# saturation_main.net
KiCad netlist of a schematic drawn in EAGLE
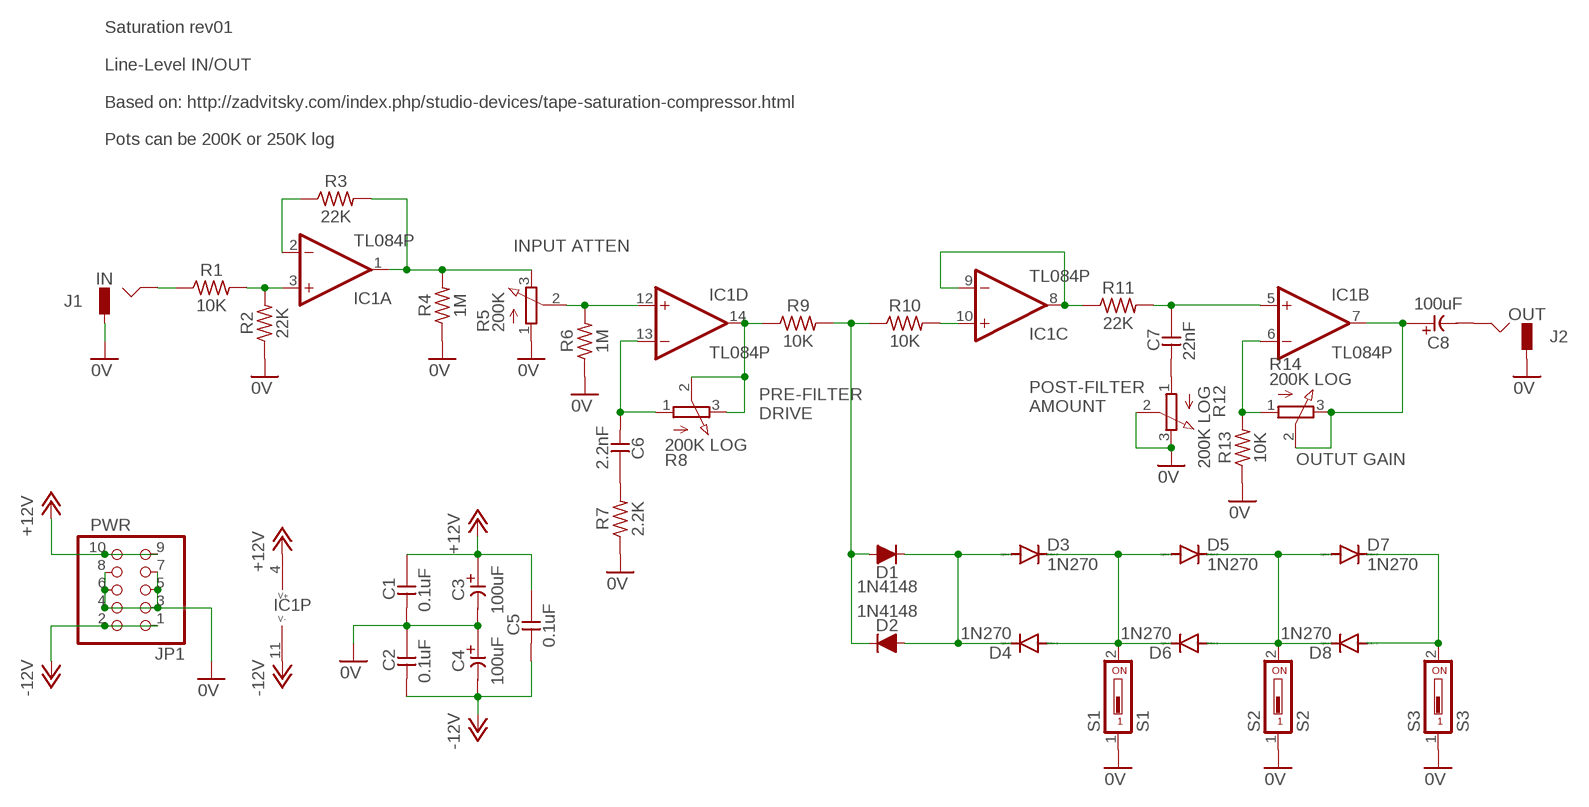
[diagram p0: schematic, sheet 1]

(export (version "E")
  (design (tool "Eeschema 10.0.6"))
  (components
    (comp (ref "C1")
      (value "0.1uF")
      (footprint "eagle-import:C025-024X044")
      (libsource (lib "eagle-import") (part "CC-US025-024X044"))
    )
    (comp (ref "C2")
      (value "0.1uF")
      (footprint "eagle-import:C025-024X044")
      (libsource (lib "eagle-import") (part "CC-US025-024X044"))
    )
    (comp (ref "C3")
      (value "100uF")
      (footprint "eagle-import:E5-8,5")
      (libsource (lib "eagle-import") (part "CE-USE5-8.5"))
    )
    (comp (ref "C4")
      (value "100uF")
      (footprint "eagle-import:E5-8,5")
      (libsource (lib "eagle-import") (part "CE-USE5-8.5"))
    )
    (comp (ref "C5")
      (value "0.1uF")
      (footprint "eagle-import:C025-024X044")
      (libsource (lib "eagle-import") (part "CC-US025-024X044"))
    )
    (comp (ref "C6")
      (value "2.2nF")
      (footprint "eagle-import:C025-024X044")
      (libsource (lib "eagle-import") (part "CC-US025-024X044"))
    )
    (comp (ref "C7")
      (value "22nF")
      (footprint "eagle-import:C025-024X044")
      (libsource (lib "eagle-import") (part "CC-US025-024X044"))
    )
    (comp (ref "C8")
      (value "100uF")
      (footprint "eagle-import:E5-8,5")
      (libsource (lib "eagle-import") (part "CE-USE5-8.5"))
    )
    (comp (ref "D1")
      (value "1N4148")
      (footprint "eagle-import:DO34-5")
      (libsource (lib "eagle-import") (part "1N4148"))
    )
    (comp (ref "D2")
      (value "1N4148")
      (footprint "eagle-import:DO34-5")
      (libsource (lib "eagle-import") (part "1N4148"))
    )
    (comp (ref "D3")
      (value "1N270")
      (footprint "eagle-import:DO07")
      (libsource (lib "eagle-import") (part "1N270"))
    )
    (comp (ref "D4")
      (value "1N270")
      (footprint "eagle-import:DO07")
      (libsource (lib "eagle-import") (part "1N270"))
    )
    (comp (ref "D5")
      (value "1N270")
      (footprint "eagle-import:DO07")
      (libsource (lib "eagle-import") (part "1N270"))
    )
    (comp (ref "D6")
      (value "1N270")
      (footprint "eagle-import:DO07")
      (libsource (lib "eagle-import") (part "1N270"))
    )
    (comp (ref "D7")
      (value "1N270")
      (footprint "eagle-import:DO07")
      (libsource (lib "eagle-import") (part "1N270"))
    )
    (comp (ref "D8")
      (value "1N270")
      (footprint "eagle-import:DO07")
      (libsource (lib "eagle-import") (part "1N270"))
    )
    (comp (ref "IC1")
      (value "TL084P")
      (footprint "eagle-import:DIL14")
      (libsource (lib "eagle-import") (part "TL084P"))
    )
    (comp (ref "J1")
      (value "IN")
      (footprint "eagle-import:JACK-M")
      (libsource (lib "eagle-import") (part "JACK-M"))
    )
    (comp (ref "J2")
      (value "OUT")
      (footprint "eagle-import:JACK-M")
      (libsource (lib "eagle-import") (part "JACK-M"))
    )
    (comp (ref "JP1")
      (value "PWR")
      (footprint "eagle-import:2X05")
      (libsource (lib "eagle-import") (part "PINHD-2X5"))
    )
    (comp (ref "R1")
      (value "10K")
      (footprint "eagle-import:0207_7")
      (libsource (lib "eagle-import") (part "R"))
    )
    (comp (ref "R2")
      (value "22K")
      (footprint "eagle-import:0207_7")
      (libsource (lib "eagle-import") (part "R"))
    )
    (comp (ref "R3")
      (value "22K")
      (footprint "eagle-import:0207_7")
      (libsource (lib "eagle-import") (part "R"))
    )
    (comp (ref "R4")
      (value "1M")
      (footprint "eagle-import:0207_7")
      (libsource (lib "eagle-import") (part "R"))
    )
    (comp (ref "R5")
      (value "200K")
      (footprint "eagle-import:3RP_1610N")
      (libsource (lib "eagle-import") (part "3RP/1610N"))
    )
    (comp (ref "R6")
      (value "1M")
      (footprint "eagle-import:0207_7")
      (libsource (lib "eagle-import") (part "R"))
    )
    (comp (ref "R7")
      (value "2.2K")
      (footprint "eagle-import:0207_7")
      (libsource (lib "eagle-import") (part "R"))
    )
    (comp (ref "R8")
      (value "200K LOG")
      (footprint "eagle-import:3RP_1610N")
      (libsource (lib "eagle-import") (part "3RP/1610N"))
    )
    (comp (ref "R9")
      (value "10K")
      (footprint "eagle-import:0207_7")
      (libsource (lib "eagle-import") (part "R"))
    )
    (comp (ref "R10")
      (value "10K")
      (footprint "eagle-import:0207_7")
      (libsource (lib "eagle-import") (part "R"))
    )
    (comp (ref "R11")
      (value "22K")
      (footprint "eagle-import:0207_7")
      (libsource (lib "eagle-import") (part "R"))
    )
    (comp (ref "R12")
      (value "200K LOG")
      (footprint "eagle-import:3RP_1610N")
      (libsource (lib "eagle-import") (part "3RP/1610N"))
    )
    (comp (ref "R13")
      (value "10K")
      (footprint "eagle-import:0207_7")
      (libsource (lib "eagle-import") (part "R"))
    )
    (comp (ref "R14")
      (value "200K LOG")
      (footprint "eagle-import:3RP_1610N")
      (libsource (lib "eagle-import") (part "3RP/1610N"))
    )
    (comp (ref "S1")
      (value "S1")
      (footprint "eagle-import:DS-01")
      (libsource (lib "eagle-import") (part "DS01"))
    )
    (comp (ref "S2")
      (value "S2")
      (footprint "eagle-import:DS-01")
      (libsource (lib "eagle-import") (part "DS01"))
    )
    (comp (ref "S3")
      (value "S3")
      (footprint "eagle-import:DS-01")
      (libsource (lib "eagle-import") (part "DS01"))
    )
  )
  (nets
    (net (code "1") (name "+12V") (class "Default")
      (node (ref "C1") (pin "1") (pinfunction "1_1") (pintype "passive"))
      (node (ref "C3") (pin "+") (pinfunction "+_+") (pintype "passive"))
      (node (ref "C5") (pin "1") (pinfunction "1_1") (pintype "passive"))
      (node (ref "IC1") (pin "4") (pinfunction "V+_4") (pintype "power_in"))
      (node (ref "JP1") (pin "10") (pinfunction "10_10") (pintype "passive"))
      (node (ref "JP1") (pin "9") (pinfunction "9_9") (pintype "passive"))
    )
    (net (code "2") (name "-12V") (class "Default")
      (node (ref "C2") (pin "2") (pinfunction "2_2") (pintype "passive"))
      (node (ref "C4") (pin "-") (pinfunction "-_-") (pintype "passive"))
      (node (ref "C5") (pin "2") (pinfunction "2_2") (pintype "passive"))
      (node (ref "IC1") (pin "11") (pinfunction "V-_11") (pintype "power_in"))
      (node (ref "JP1") (pin "1") (pinfunction "1_1") (pintype "passive"))
      (node (ref "JP1") (pin "2") (pinfunction "2_2") (pintype "passive"))
    )
    (net (code "3") (name "0V") (class "Default")
      (node (ref "C1") (pin "2") (pinfunction "2_2") (pintype "passive"))
      (node (ref "C2") (pin "1") (pinfunction "1_1") (pintype "passive"))
      (node (ref "C3") (pin "-") (pinfunction "-_-") (pintype "passive"))
      (node (ref "C4") (pin "+") (pinfunction "+_+") (pintype "passive"))
      (node (ref "J1") (pin "GND") (pinfunction "GND_GND") (pintype "bidirectional"))
      (node (ref "J2") (pin "GND") (pinfunction "GND_GND") (pintype "bidirectional"))
      (node (ref "JP1") (pin "3") (pinfunction "3_3") (pintype "passive"))
      (node (ref "JP1") (pin "4") (pinfunction "4_4") (pintype "passive"))
      (node (ref "JP1") (pin "5") (pinfunction "5_5") (pintype "passive"))
      (node (ref "JP1") (pin "6") (pinfunction "6_6") (pintype "passive"))
      (node (ref "JP1") (pin "7") (pinfunction "7_7") (pintype "passive"))
      (node (ref "JP1") (pin "8") (pinfunction "8_8") (pintype "passive"))
      (node (ref "R12") (pin "2") (pinfunction "S_2") (pintype "passive"))
      (node (ref "R12") (pin "3") (pinfunction "E_3") (pintype "passive"))
      (node (ref "R13") (pin "1") (pinfunction "1_1") (pintype "passive"))
      (node (ref "R2") (pin "1") (pinfunction "1_1") (pintype "passive"))
      (node (ref "R4") (pin "1") (pinfunction "1_1") (pintype "passive"))
      (node (ref "R5") (pin "1") (pinfunction "A_1") (pintype "passive"))
      (node (ref "R6") (pin "1") (pinfunction "1_1") (pintype "passive"))
      (node (ref "R7") (pin "1") (pinfunction "1_1") (pintype "passive"))
      (node (ref "S1") (pin "1") (pinfunction "1_1") (pintype "passive"))
      (node (ref "S2") (pin "1") (pinfunction "1_1") (pintype "passive"))
      (node (ref "S3") (pin "1") (pinfunction "1_1") (pintype "passive"))
    )
    (net (code "4") (name "Net-(C6-Pad1)") (class "Default")
      (node (ref "C6") (pin "1") (pinfunction "1_1") (pintype "passive"))
      (node (ref "R7") (pin "2") (pinfunction "2_2") (pintype "passive"))
    )
    (net (code "5") (name "Net-(C8-Pad-)") (class "Default")
      (node (ref "C8") (pin "-") (pinfunction "-_-") (pintype "passive"))
      (node (ref "J2") (pin "HOT") (pinfunction "HOT_HOT") (pintype "bidirectional"))
    )
    (net (code "6") (name "Net-(D1-PadA)") (class "Default")
      (node (ref "D1") (pin "A") (pinfunction "A_A") (pintype "passive"))
      (node (ref "D2") (pin "C") (pinfunction "C_C") (pintype "passive"))
      (node (ref "R10") (pin "1") (pinfunction "1_1") (pintype "passive"))
      (node (ref "R9") (pin "2") (pinfunction "2_2") (pintype "passive"))
    )
    (net (code "7") (name "Net-(D1-PadC)") (class "Default")
      (node (ref "D1") (pin "C") (pinfunction "C_C") (pintype "passive"))
      (node (ref "D2") (pin "A") (pinfunction "A_A") (pintype "passive"))
      (node (ref "D3") (pin "A") (pinfunction "A_A") (pintype "passive"))
      (node (ref "D4") (pin "C") (pinfunction "C_C") (pintype "passive"))
    )
    (net (code "8") (name "Net-(D3-PadC)") (class "Default")
      (node (ref "D3") (pin "C") (pinfunction "C_C") (pintype "passive"))
      (node (ref "D4") (pin "A") (pinfunction "A_A") (pintype "passive"))
      (node (ref "D5") (pin "A") (pinfunction "A_A") (pintype "passive"))
      (node (ref "D6") (pin "C") (pinfunction "C_C") (pintype "passive"))
      (node (ref "S1") (pin "2") (pinfunction "2_2") (pintype "passive"))
    )
    (net (code "9") (name "Net-(D5-PadC)") (class "Default")
      (node (ref "D5") (pin "C") (pinfunction "C_C") (pintype "passive"))
      (node (ref "D6") (pin "A") (pinfunction "A_A") (pintype "passive"))
      (node (ref "D7") (pin "A") (pinfunction "A_A") (pintype "passive"))
      (node (ref "D8") (pin "C") (pinfunction "C_C") (pintype "passive"))
      (node (ref "S2") (pin "2") (pinfunction "2_2") (pintype "passive"))
    )
    (net (code "10") (name "Net-(D7-PadC)") (class "Default")
      (node (ref "D7") (pin "C") (pinfunction "C_C") (pintype "passive"))
      (node (ref "D8") (pin "A") (pinfunction "A_A") (pintype "passive"))
      (node (ref "S3") (pin "2") (pinfunction "2_2") (pintype "passive"))
    )
    (net (code "11") (name "Net-(IC1A-+IN)") (class "Default")
      (node (ref "IC1") (pin "3") (pinfunction "+IN_3") (pintype "input"))
      (node (ref "R1") (pin "2") (pinfunction "2_2") (pintype "passive"))
      (node (ref "R2") (pin "2") (pinfunction "2_2") (pintype "passive"))
    )
    (net (code "12") (name "Net-(IC1A--IN)") (class "Default")
      (node (ref "IC1") (pin "2") (pinfunction "-IN_2") (pintype "input"))
      (node (ref "R3") (pin "1") (pinfunction "1_1") (pintype "passive"))
    )
    (net (code "13") (name "Net-(IC1A-OUT)") (class "Default")
      (node (ref "IC1") (pin "1") (pinfunction "OUT_1") (pintype "output"))
      (node (ref "R3") (pin "2") (pinfunction "2_2") (pintype "passive"))
      (node (ref "R4") (pin "2") (pinfunction "2_2") (pintype "passive"))
      (node (ref "R5") (pin "3") (pinfunction "E_3") (pintype "passive"))
    )
    (net (code "14") (name "Net-(IC1B-+IN)") (class "Default")
      (node (ref "C7") (pin "1") (pinfunction "1_1") (pintype "passive"))
      (node (ref "IC1") (pin "5") (pinfunction "+IN_5") (pintype "input"))
      (node (ref "R11") (pin "2") (pinfunction "2_2") (pintype "passive"))
    )
    (net (code "15") (name "Net-(IC1B--IN)") (class "Default")
      (node (ref "IC1") (pin "6") (pinfunction "-IN_6") (pintype "input"))
      (node (ref "R13") (pin "2") (pinfunction "2_2") (pintype "passive"))
      (node (ref "R14") (pin "1") (pinfunction "A_1") (pintype "passive"))
    )
    (net (code "16") (name "Net-(IC1B-OUT)") (class "Default")
      (node (ref "C8") (pin "+") (pinfunction "+_+") (pintype "passive"))
      (node (ref "IC1") (pin "7") (pinfunction "OUT_7") (pintype "output"))
      (node (ref "R14") (pin "2") (pinfunction "S_2") (pintype "passive"))
      (node (ref "R14") (pin "3") (pinfunction "E_3") (pintype "passive"))
    )
    (net (code "17") (name "Net-(IC1C-+IN)") (class "Default")
      (node (ref "IC1") (pin "10") (pinfunction "+IN_10") (pintype "input"))
      (node (ref "R10") (pin "2") (pinfunction "2_2") (pintype "passive"))
    )
    (net (code "18") (name "Net-(IC1C--IN)") (class "Default")
      (node (ref "IC1") (pin "8") (pinfunction "OUT_8") (pintype "output"))
      (node (ref "IC1") (pin "9") (pinfunction "-IN_9") (pintype "input"))
      (node (ref "R11") (pin "1") (pinfunction "1_1") (pintype "passive"))
    )
    (net (code "19") (name "Net-(IC1D-+IN)") (class "Default")
      (node (ref "IC1") (pin "12") (pinfunction "+IN_12") (pintype "input"))
      (node (ref "R5") (pin "2") (pinfunction "S_2") (pintype "passive"))
      (node (ref "R6") (pin "2") (pinfunction "2_2") (pintype "passive"))
    )
    (net (code "20") (name "Net-(IC1D--IN)") (class "Default")
      (node (ref "C6") (pin "2") (pinfunction "2_2") (pintype "passive"))
      (node (ref "IC1") (pin "13") (pinfunction "-IN_13") (pintype "input"))
      (node (ref "R8") (pin "1") (pinfunction "A_1") (pintype "passive"))
    )
    (net (code "21") (name "Net-(IC1D-OUT)") (class "Default")
      (node (ref "IC1") (pin "14") (pinfunction "OUT_14") (pintype "output"))
      (node (ref "R8") (pin "2") (pinfunction "S_2") (pintype "passive"))
      (node (ref "R8") (pin "3") (pinfunction "E_3") (pintype "passive"))
      (node (ref "R9") (pin "1") (pinfunction "1_1") (pintype "passive"))
    )
    (net (code "22") (name "Net-(J1-PadHOT)") (class "Default")
      (node (ref "J1") (pin "HOT") (pinfunction "HOT_HOT") (pintype "bidirectional"))
      (node (ref "R1") (pin "1") (pinfunction "1_1") (pintype "passive"))
    )
    (net (code "23") (name "Net-(R12-A)") (class "Default")
      (node (ref "C7") (pin "2") (pinfunction "2_2") (pintype "passive"))
      (node (ref "R12") (pin "1") (pinfunction "A_1") (pintype "passive"))
    )
  )
)
